# T35_7_MEMORY.net
KiCad netlist of a schematic drawn in Altium Designer
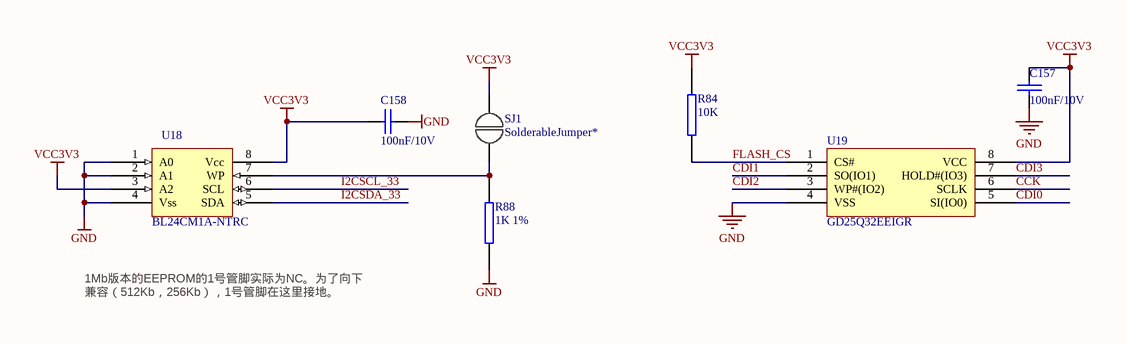
[diagram p0: T35_7_MEMORY.SchDoc]

(export (version "E")
  (design (tool "Eeschema 10.0.6"))
  (components
    (comp (ref "C157")
      (value "100nF/10V")
      (footprint "0201CS")
      (description "贴片电容")
      (libsource (lib "*") (part "CAP"))
    )
    (comp (ref "C158")
      (value "100nF/10V")
      (footprint "0201CS")
      (description "贴片电容")
      (libsource (lib "*") (part "CAP"))
    )
    (comp (ref "R84")
      (value "10K")
      (footprint "0201RS")
      (description "贴片电阻")
      (libsource (lib "*") (part "RES2"))
    )
    (comp (ref "R88")
      (value "1K 1%")
      (footprint "0402RS")
      (description "贴片电阻")
      (libsource (lib "") (part "RES2_1"))
    )
    (comp (ref "SJ1")
      (value "SolderableJumper*")
      (footprint "SJ")
      (libsource (lib "T35-V2") (part "SolderableJumper"))
    )
    (comp (ref "U18")
      (value "BL24CM1A-NTRC")
      (footprint "UDFN-8LL")
      (description "EEPROM芯片")
      (libsource (lib "*") (part "24LC00"))
    )
    (comp (ref "U19")
      (value "GD25Q32EEIGR")
      (footprint "SON127P600-8N-USON8")
      (description "SPI Flash")
      (libsource (lib "LEC") (part "GD25Q64ESIG"))
    )
  )
  (nets
    (net (code "1") (name "/CCK") (class "Default")
      (node (ref "U19") (pin "6") (pinfunction "SCLK_6") (pintype "passive"))
    )
    (net (code "2") (name "/CDI0") (class "Default")
      (node (ref "U19") (pin "5") (pinfunction "SI(IO0)_5") (pintype "passive"))
    )
    (net (code "3") (name "/CDI1") (class "Default")
      (node (ref "U19") (pin "2") (pinfunction "SO(IO1)_2") (pintype "passive"))
    )
    (net (code "4") (name "/CDI2") (class "Default")
      (node (ref "U19") (pin "3") (pinfunction "WP#(IO2)_3") (pintype "passive"))
    )
    (net (code "5") (name "/CDI3") (class "Default")
      (node (ref "U19") (pin "7") (pinfunction "HOLD#(IO3)_7") (pintype "passive"))
    )
    (net (code "6") (name "/FLASH_CS") (class "Default")
      (node (ref "R84") (pin "1") (pinfunction "1_1") (pintype "passive"))
      (node (ref "U19") (pin "1") (pinfunction "CS#_1") (pintype "passive"))
    )
    (net (code "7") (name "/I2CSCL_33") (class "Default")
      (node (ref "U18") (pin "6") (pinfunction "SCL_6") (pintype "bidirectional"))
    )
    (net (code "8") (name "/I2CSDA_33") (class "Default")
      (node (ref "U18") (pin "5") (pinfunction "SDA_5") (pintype "bidirectional"))
    )
    (net (code "9") (name "GND") (class "Default")
      (node (ref "C157") (pin "2") (pinfunction "2_2") (pintype "passive"))
      (node (ref "C158") (pin "1") (pinfunction "1_1") (pintype "passive"))
      (node (ref "R88") (pin "2") (pinfunction "2_2") (pintype "passive"))
      (node (ref "U18") (pin "1") (pinfunction "A0_1") (pintype "input"))
      (node (ref "U18") (pin "2") (pinfunction "A1_2") (pintype "input"))
      (node (ref "U18") (pin "4") (pinfunction "Vss_4") (pintype "power_in"))
      (node (ref "U19") (pin "4") (pinfunction "VSS_4") (pintype "passive"))
    )
    (net (code "10") (name "Net-(U18-WP)") (class "Default")
      (node (ref "R88") (pin "1") (pinfunction "1_1") (pintype "passive"))
      (node (ref "SJ1") (pin "2") (pinfunction "2_2") (pintype "passive"))
      (node (ref "U18") (pin "7") (pinfunction "WP_7") (pintype "input"))
    )
    (net (code "11") (name "VCC3V3") (class "Default")
      (node (ref "C157") (pin "1") (pinfunction "1_1") (pintype "passive"))
      (node (ref "C158") (pin "2") (pinfunction "2_2") (pintype "passive"))
      (node (ref "R84") (pin "2") (pinfunction "2_2") (pintype "passive"))
      (node (ref "SJ1") (pin "1") (pinfunction "1_1") (pintype "passive"))
      (node (ref "U18") (pin "3") (pinfunction "A2_3") (pintype "input"))
      (node (ref "U18") (pin "8") (pinfunction "Vcc_8") (pintype "power_in"))
      (node (ref "U19") (pin "8") (pinfunction "VCC_8") (pintype "passive"))
    )
  )
)
